# opt_H_Bridge.net
KiCad netlist of a schematic drawn in EAGLE
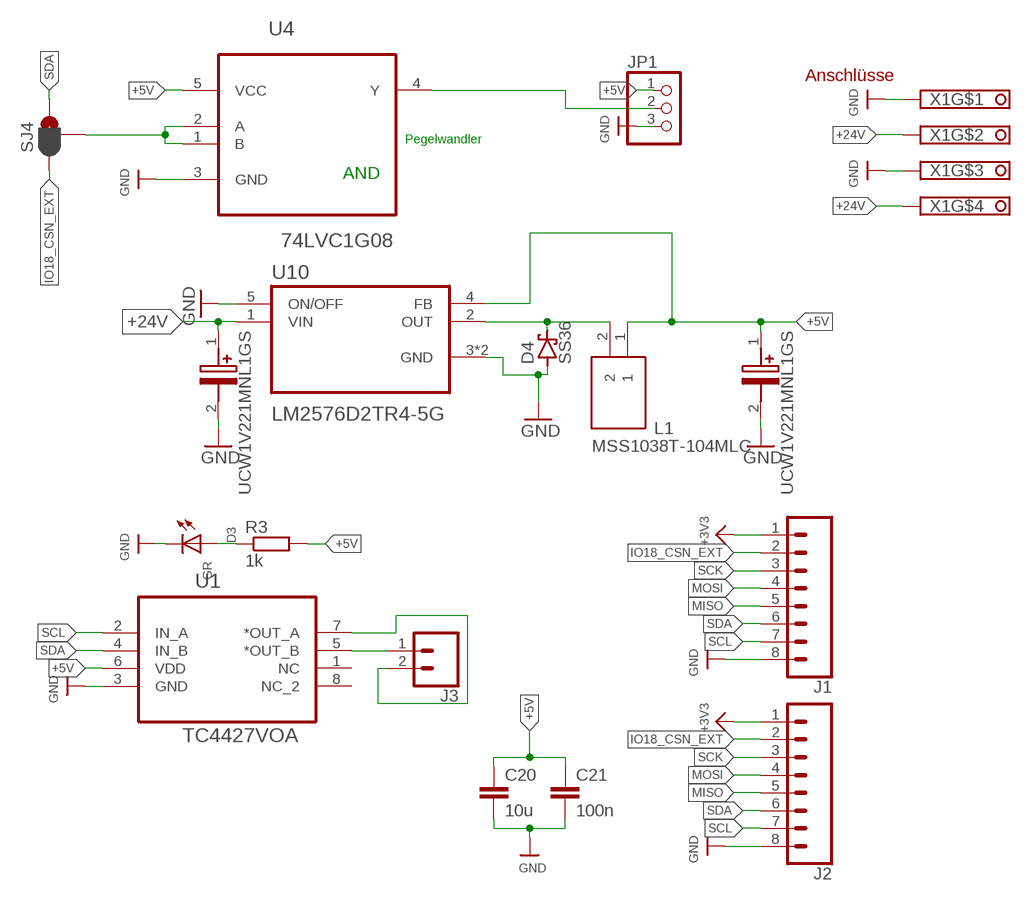
[diagram p0: schematic, sheet 1]

(export (version "E")
  (design (tool "Eeschema 10.0.6"))
  (components
    (comp (ref "C1")
      (value "UCW1V221MNL1GS")
      (footprint "eagle-import:UWT(8X10)")
      (fields (field (name "MF") "Nichicon"))
      (libsource (lib "eagle-import") (part "UCW1V221MNL1GS"))
    )
    (comp (ref "C20")
      (value "10u")
      (footprint "eagle-import:C0805")
      (libsource (lib "eagle-import") (part "C-EUC0805"))
    )
    (comp (ref "C21")
      (value "100n")
      (footprint "eagle-import:C0805")
      (libsource (lib "eagle-import") (part "C-EUC0805"))
    )
    (comp (ref "C31")
      (value "UCW1V221MNL1GS")
      (footprint "eagle-import:UWT(8X10)")
      (fields (field (name "MF") "Nichicon"))
      (libsource (lib "eagle-import") (part "UCW1V221MNL1GS"))
    )
    (comp (ref "D3")
      (value "GR")
      (footprint "eagle-import:CHIP-LED0805")
      (libsource (lib "eagle-import") (part "LEDCHIP-LED0805"))
    )
    (comp (ref "D4")
      (value "SS36")
      (footprint "eagle-import:SMC")
      (libsource (lib "eagle-import") (part "SCHOTTKY-DIODESMC"))
    )
    (comp (ref "J1")
      (value "CONN_08BM08B-SRSS-TB")
      (footprint "eagle-import:BM08B-SRSS-TB")
      (libsource (lib "eagle-import") (part "CONN_08BM08B-SRSS-TB"))
    )
    (comp (ref "J2")
      (value "CONN_08BM08B-SRSS-TB")
      (footprint "eagle-import:BM08B-SRSS-TB")
      (libsource (lib "eagle-import") (part "CONN_08BM08B-SRSS-TB"))
    )
    (comp (ref "J3")
      (value "CONN_023.5MM")
      (footprint "eagle-import:SCREWTERMINAL-3.5MM-2")
      (libsource (lib "eagle-import") (part "CONN_023.5MM"))
    )
    (comp (ref "JP1")
      (value "PINHD-1X3")
      (footprint "eagle-import:1X03")
      (libsource (lib "eagle-import") (part "PINHD-1X3"))
    )
    (comp (ref "L1")
      (value "MSS1038T-104MLC")
      (footprint "eagle-import:INDPM102100X400N")
      (fields
        (field (name "MANUFACTURER_PART_NUMBER") "MSS1038-473MLC")
        (field (name "MOUSER_PART_NUMBER") "994-MSS1038-473MLC")
      )
      (libsource (lib "eagle-import") (part "MSS1038-473MLC"))
    )
    (comp (ref "R3")
      (value "1k")
      (footprint "eagle-import:R0805")
      (libsource (lib "eagle-import") (part "R-EU_R0805"))
    )
    (comp (ref "SJ4")
      (value "JUMPER_PAD-3-1&2_NC_BY_PASTE")
      (footprint "eagle-import:PAD-HUMPER-3-1&2_NC_BY_PASTE_YES_SILK_FULL_BOX")
      (libsource (lib "eagle-import") (part "JUMPER_PAD-3-1&2_NC_BY_PASTE"))
    )
    (comp (ref "U1")
      (value "TC4427VOA")
      (footprint "eagle-import:SOIC127P600X175-8N")
      (fields (field (name "MF") "Microchip"))
      (libsource (lib "eagle-import") (part "TC4427VOA"))
    )
    (comp (ref "U4")
      (value "74LVC1G08")
      (footprint "eagle-import:SOT65P210X110-5N")
      (fields (field (name "MF") "Nexperia") (field (name "MP") "74LVC1G00GW"))
      (libsource (lib "eagle-import") (part "74LVC1G00GW"))
    )
    (comp (ref "U10")
      (value "LM2576D2TR4-5G")
      (footprint "eagle-import:VREG_TPS79625KTTR")
      (fields (field (name "MF") "Texas Instruments") (field (name "MP") "LM2576HVSX-ADJ/NOPB"))
      (libsource (lib "eagle-import") (part "LM2576HVSX-ADJ/NOPB"))
    )
    (comp (ref "X1")
      (value "PT11304HBBN")
      (footprint "eagle-import:TYP184_FT")
      (libsource (lib "eagle-import") (part "TYP184"))
    )
  )
  (nets
    (net (code "1") (name "+3V3") (class "Default")
      (node (ref "J1") (pin "1") (pinfunction "1_1") (pintype "passive"))
      (node (ref "J2") (pin "1") (pinfunction "1_1") (pintype "passive"))
    )
    (net (code "2") (name "+5V") (class "Default")
      (node (ref "C1") (pin "1") (pinfunction "+_1") (pintype "bidirectional"))
      (node (ref "C20") (pin "1") (pinfunction "1_1") (pintype "passive"))
      (node (ref "C21") (pin "1") (pinfunction "1_1") (pintype "passive"))
      (node (ref "JP1") (pin "1") (pinfunction "1_1") (pintype "passive"))
      (node (ref "L1") (pin "1") (pinfunction "1_1") (pintype "bidirectional"))
      (node (ref "R3") (pin "2") (pinfunction "2_2") (pintype "passive"))
      (node (ref "U1") (pin "6") (pinfunction "VDD_6") (pintype "power_in"))
      (node (ref "U10") (pin "4") (pinfunction "FB_4") (pintype "output"))
      (node (ref "U4") (pin "5") (pinfunction "VCC_5") (pintype "power_in"))
    )
    (net (code "3") (name "+24V") (class "Default")
      (node (ref "C31") (pin "1") (pinfunction "+_1") (pintype "bidirectional"))
      (node (ref "U10") (pin "1") (pinfunction "VIN_1") (pintype "input"))
      (node (ref "X1") (pin "2") (pinfunction "K_2") (pintype "passive"))
      (node (ref "X1") (pin "4") (pinfunction "K_4") (pintype "passive"))
    )
    (net (code "4") (name "GND") (class "Default")
      (node (ref "C1") (pin "2") (pinfunction "-_2") (pintype "bidirectional"))
      (node (ref "C20") (pin "2") (pinfunction "2_2") (pintype "passive"))
      (node (ref "C21") (pin "2") (pinfunction "2_2") (pintype "passive"))
      (node (ref "C31") (pin "2") (pinfunction "-_2") (pintype "bidirectional"))
      (node (ref "D3") (pin "C") (pinfunction "C_C") (pintype "passive"))
      (node (ref "D4") (pin "A") (pinfunction "A_A") (pintype "passive"))
      (node (ref "J1") (pin "8") (pinfunction "8_8") (pintype "passive"))
      (node (ref "J2") (pin "8") (pinfunction "8_8") (pintype "passive"))
      (node (ref "JP1") (pin "3") (pinfunction "3_3") (pintype "passive"))
      (node (ref "U1") (pin "3") (pinfunction "GND_3") (pintype "passive"))
      (node (ref "U10") (pin "3") (pinfunction "GND_3") (pintype "power_in"))
      (node (ref "U10") (pin "5") (pinfunction "ON/OFF_5") (pintype "input"))
      (node (ref "U10") (pin "6") (pinfunction "GND_6") (pintype "power_in"))
      (node (ref "U4") (pin "3") (pinfunction "GND_3") (pintype "passive"))
      (node (ref "X1") (pin "1") (pinfunction "K_1") (pintype "passive"))
      (node (ref "X1") (pin "3") (pinfunction "K_3") (pintype "passive"))
    )
    (net (code "5") (name "IO18_CSN_EXT") (class "Default")
      (node (ref "J1") (pin "2") (pinfunction "2_2") (pintype "passive"))
      (node (ref "J2") (pin "2") (pinfunction "2_2") (pintype "passive"))
      (node (ref "SJ4") (pin "1") (pinfunction "1_1") (pintype "passive"))
    )
    (net (code "6") (name "MISO") (class "Default")
      (node (ref "J1") (pin "5") (pinfunction "5_5") (pintype "passive"))
      (node (ref "J2") (pin "5") (pinfunction "5_5") (pintype "passive"))
    )
    (net (code "7") (name "MOSI") (class "Default")
      (node (ref "J1") (pin "4") (pinfunction "4_4") (pintype "passive"))
      (node (ref "J2") (pin "4") (pinfunction "4_4") (pintype "passive"))
    )
    (net (code "8") (name "Net-(D3-PadA)") (class "Default")
      (node (ref "D3") (pin "A") (pinfunction "A_A") (pintype "passive"))
      (node (ref "R3") (pin "1") (pinfunction "1_1") (pintype "passive"))
    )
    (net (code "9") (name "Net-(U1-*OUT_A)") (class "Default")
      (node (ref "J3") (pin "2") (pinfunction "2_2") (pintype "passive"))
      (node (ref "U1") (pin "7") (pinfunction "*OUT_A_7") (pintype "output"))
    )
    (net (code "10") (name "Net-(U1-*OUT_B)") (class "Default")
      (node (ref "J3") (pin "1") (pinfunction "1_1") (pintype "passive"))
      (node (ref "U1") (pin "5") (pinfunction "*OUT_B_5") (pintype "output"))
    )
    (net (code "11") (name "Net-(U4-A)") (class "Default")
      (node (ref "SJ4") (pin "2") (pinfunction "2_2") (pintype "passive"))
      (node (ref "U4") (pin "1") (pinfunction "B_1") (pintype "input"))
      (node (ref "U4") (pin "2") (pinfunction "A_2") (pintype "input"))
    )
    (net (code "12") (name "Net-(U4-Y)") (class "Default")
      (node (ref "JP1") (pin "2") (pinfunction "2_2") (pintype "passive"))
      (node (ref "U4") (pin "4") (pinfunction "Y_4") (pintype "output"))
    )
    (net (code "13") (name "Net-(U10-OUT)") (class "Default")
      (node (ref "D4") (pin "C") (pinfunction "C_C") (pintype "passive"))
      (node (ref "L1") (pin "2") (pinfunction "2_2") (pintype "bidirectional"))
      (node (ref "U10") (pin "2") (pinfunction "OUT_2") (pintype "output"))
    )
    (net (code "14") (name "SCK") (class "Default")
      (node (ref "J1") (pin "3") (pinfunction "3_3") (pintype "passive"))
      (node (ref "J2") (pin "3") (pinfunction "3_3") (pintype "passive"))
    )
    (net (code "15") (name "SCL") (class "Default")
      (node (ref "J1") (pin "7") (pinfunction "7_7") (pintype "passive"))
      (node (ref "J2") (pin "7") (pinfunction "7_7") (pintype "passive"))
      (node (ref "U1") (pin "2") (pinfunction "IN_A_2") (pintype "input"))
    )
    (net (code "16") (name "SDA") (class "Default")
      (node (ref "J1") (pin "6") (pinfunction "6_6") (pintype "passive"))
      (node (ref "J2") (pin "6") (pinfunction "6_6") (pintype "passive"))
      (node (ref "SJ4") (pin "3") (pinfunction "3_3") (pintype "passive"))
      (node (ref "U1") (pin "4") (pinfunction "IN_B_4") (pintype "input"))
    )
    (net (code "17") (name "unconnected-(U1-NC-Pad1)") (class "Default")
      (node (ref "U1") (pin "1") (pinfunction "NC_1") (pintype "no_connect"))
    )
    (net (code "18") (name "unconnected-(U1-NC_2-Pad8)") (class "Default")
      (node (ref "U1") (pin "8") (pinfunction "NC_2_8") (pintype "no_connect"))
    )
  )
)
